# PWR_DIST.net
KiCad netlist of a schematic drawn in Altium Designer
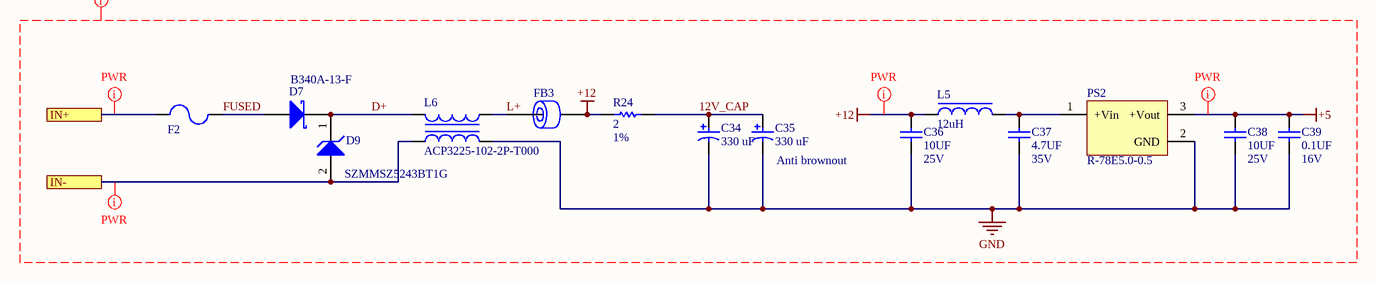
[diagram p0: PWR_DIST.SchDoc]

(export (version "E")
  (design (tool "Eeschema 10.0.6"))
  (components
    (comp (ref "C34")
      (value "UUD1V331MNL1GS")
      (footprint "NIC-CAPA2-10X10_V")
      (fields (field (name "MANUFACTURER") "Nichicon") (field (name "RATED CAPACITANCE") "330 uF"))
      (libsource (lib "AERO Parts") (part "UUD1V331MNL1GS"))
    )
    (comp (ref "C35")
      (value "UUD1V331MNL1GS")
      (footprint "NIC-CAPA2-10X10_V")
      (fields (field (name "MANUFACTURER") "Nichicon") (field (name "RATED CAPACITANCE") "330 uF"))
      (libsource (lib "AERO Parts") (part "UUD1V331MNL1GS"))
    )
    (comp (ref "C36")
      (value "CAP 0603 10UF 25V 20% X5R")
      (footprint "0603_CAP")
      (description "Capacitor Surface Mount 0603 Footprint 10UF 25V 20% Tolerance Ceramic X5R")
      (fields
        (field (name "VAL") "10UF")
        (field (name "VOL") "25V")
        (field (name "MANUFACTURER") "Various")
        (field (name "VOLTAGE") "25V")
      )
      (libsource (lib "Passive Components") (part "cap"))
    )
    (comp (ref "C37")
      (value "CAP 0603 4.7UF 35V 10% X5R")
      (footprint "0603_CAP")
      (description "Capacitor Surface Mount 0603 Footprint 47UF 35V 10% Tolerance Ceramic X5R")
      (fields
        (field (name "VAL") "4.7UF")
        (field (name "VOL") "35V")
        (field (name "MANUFACTURER") "Various")
        (field (name "VOLTAGE") "35V")
      )
      (libsource (lib "Passive Components") (part "cap"))
    )
    (comp (ref "C38")
      (value "CAP 0603 10UF 25V 20% X5R")
      (footprint "0603_CAP")
      (description "Capacitor Surface Mount 0603 Footprint 10UF 25V 20% Tolerance Ceramic X5R")
      (fields
        (field (name "VAL") "10UF")
        (field (name "VOL") "25V")
        (field (name "MANUFACTURER") "Various")
        (field (name "VOLTAGE") "25V")
      )
      (libsource (lib "Passive Components") (part "cap"))
    )
    (comp (ref "C39")
      (value "CAP 0603 0.1UF 16V 10% X7R")
      (footprint "0603_CAP")
      (description "Capacitor Surface Mount 0603 Footprint 0.1UF 16V 10% Tolerance Ceramic X7R")
      (fields
        (field (name "VAL") "0.1UF")
        (field (name "VOL") "16V")
        (field (name "MANUFACTURER") "Various")
        (field (name "VOLTAGE") "16V")
      )
      (libsource (lib "Passive Components") (part "cap"))
    )
    (comp (ref "D7")
      (value "B340A-13-F")
      (footprint "DIOD-SMA-2_V")
      (libsource (lib "Altium Content Vault") (part "DSKY-AK-2"))
    )
    (comp (ref "D9")
      (value "SZMMSZ5243BT1G")
      (footprint "ONSC-SOD-123-2-425-04_V")
      (description "Zener Voltage Regulator, 500 mW, 2-Pin SOD-123, Pb-Free, Tape and Reel")
      (fields (field (name "MANUFACTURER") "On Semiconductor"))
      (libsource (lib "Altium Content Vault") (part "ONSC-K1A2-2"))
    )
    (comp (ref "F2")
      (value "500 mA PTC")
      (footprint "1812RF")
      (description "500 mA 15 VDC PTC resettable fuse 1812 footprint")
      (fields (field (name "MANUFACTURER") "Bourns"))
      (libsource (lib "Passive Components") (part "fuse"))
    )
    (comp (ref "FB3")
      (value "Ferrite Chip 1500 Ohms")
      (footprint "0805")
      (description "Ferrite Chip 1000 mA 1500 Ohms Differential Mode - Single 0805 Footprint")
      (fields (field (name "MANUFACTURER") "Wurth Electronics"))
      (libsource (lib "Passive Components") (part "Ferrite Bead"))
    )
    (comp (ref "L5")
      (value "1225AS-H-120M=P2")
      (footprint "IND_1225AS-H-120M=P2")
      (description "1µH Shielded Wirewound Inductor 15A 4.6mOhm Nonstandard")
      (fields
        (field (name "MANUFACTURER") "Murata")
        (field (name "TOLERANCE") "20%")
        (field (name "INDUCTANCE") "12uH")
      )
      (libsource (lib "AERO Parts") (part "1225AS-H-120M=P2"))
    )
    (comp (ref "L6")
      (value "ACP3225-102-2P-T000")
      (footprint "TDK-ACP3225-102-2P-T000-4_V")
      (fields (field (name "MANUFACTURER") "TDK"))
      (libsource (lib "AERO Parts") (part "ACP3225-102-2P-T000"))
    )
    (comp (ref "PS2")
      (value "R-78E5.0-0.5")
      (footprint "RECOM_R-78E5.0-0.5_0")
      (description "IC Linear Regulator Replacement DC DC Converter 1 Output 5V 500mA 7V - 28V Input")
      (fields (field (name "DIGIKEY PART NUMBER") "945-1648-5-ND") (field (name "MANUFACTURER") "RECOM"))
      (libsource (lib "AERO Parts") (part "R-78E5.0-0.5"))
    )
    (comp (ref "R24")
      (value "RES 0805 2 1%")
      (footprint "0805_RES")
      (description "Resistor Surface Mount, 2 Ohms, 0805 Footprint, 1% Tolerance 0.125W")
      (fields
        (field (name "VAL") "2")
        (field (name "TOL") "1%")
        (field (name "MANUFACTURER") "Various")
        (field (name "TOLERANCE") "1%")
      )
      (libsource (lib "Passive Components") (part "res"))
    )
  )
  (nets
    (net (code "1") (name "+5") (class "Default")
      (node (ref "C38") (pin "2") (pinfunction "2_2") (pintype "passive"))
      (node (ref "C39") (pin "2") (pinfunction "2_2") (pintype "passive"))
      (node (ref "PS2") (pin "3") (pinfunction "+Vout_3") (pintype "power_in"))
    )
    (net (code "2") (name "+12") (class "Default")
      (node (ref "C36") (pin "2") (pinfunction "2_2") (pintype "passive"))
      (node (ref "FB3") (pin "2") (pinfunction "2_2") (pintype "passive"))
      (node (ref "L5") (pin "1") (pinfunction "1_1") (pintype "passive"))
      (node (ref "R24") (pin "1") (pinfunction "1_1") (pintype "passive"))
    )
    (net (code "3") (name "/12V_CAP") (class "Default")
      (node (ref "C34") (pin "1") (pinfunction "1_1") (pintype "passive"))
      (node (ref "C35") (pin "1") (pinfunction "1_1") (pintype "passive"))
      (node (ref "R24") (pin "2") (pinfunction "2_2") (pintype "passive"))
    )
    (net (code "4") (name "/D+") (class "Default")
      (node (ref "D7") (pin "2") (pinfunction "K_2") (pintype "passive"))
      (node (ref "D9") (pin "1") (pinfunction "K_1") (pintype "passive"))
      (node (ref "L6") (pin "1") (pinfunction "1_1") (pintype "passive"))
    )
    (net (code "5") (name "/FUSED") (class "Default")
      (node (ref "D7") (pin "1") (pinfunction "A_1") (pintype "passive"))
      (node (ref "F2") (pin "2") (pinfunction "2_2") (pintype "passive"))
    )
    (net (code "6") (name "/IN+") (class "Default")
      (node (ref "F2") (pin "1") (pinfunction "1_1") (pintype "passive"))
    )
    (net (code "7") (name "/IN-") (class "Default")
      (node (ref "D9") (pin "2") (pinfunction "A_2") (pintype "passive"))
      (node (ref "L6") (pin "2") (pinfunction "2_2") (pintype "passive"))
    )
    (net (code "8") (name "/L+") (class "Default")
      (node (ref "FB3") (pin "1") (pinfunction "1_1") (pintype "passive"))
      (node (ref "L6") (pin "4") (pinfunction "4_4") (pintype "passive"))
    )
    (net (code "9") (name "GND") (class "Default")
      (node (ref "C34") (pin "2") (pinfunction "2_2") (pintype "passive"))
      (node (ref "C35") (pin "2") (pinfunction "2_2") (pintype "passive"))
      (node (ref "C36") (pin "1") (pinfunction "1_1") (pintype "passive"))
      (node (ref "C37") (pin "1") (pinfunction "1_1") (pintype "passive"))
      (node (ref "C38") (pin "1") (pinfunction "1_1") (pintype "passive"))
      (node (ref "C39") (pin "1") (pinfunction "1_1") (pintype "passive"))
      (node (ref "L6") (pin "3") (pinfunction "3_3") (pintype "passive"))
      (node (ref "PS2") (pin "2") (pinfunction "GND_2") (pintype "power_in"))
    )
    (net (code "10") (name "Net-(PS2-+Vin)") (class "Default")
      (node (ref "C37") (pin "2") (pinfunction "2_2") (pintype "passive"))
      (node (ref "L5") (pin "2") (pinfunction "2_2") (pintype "passive"))
      (node (ref "PS2") (pin "1") (pinfunction "+Vin_1") (pintype "power_in"))
    )
  )
)
